# UbalToBal.net
KiCad netlist of a schematic drawn in EAGLE
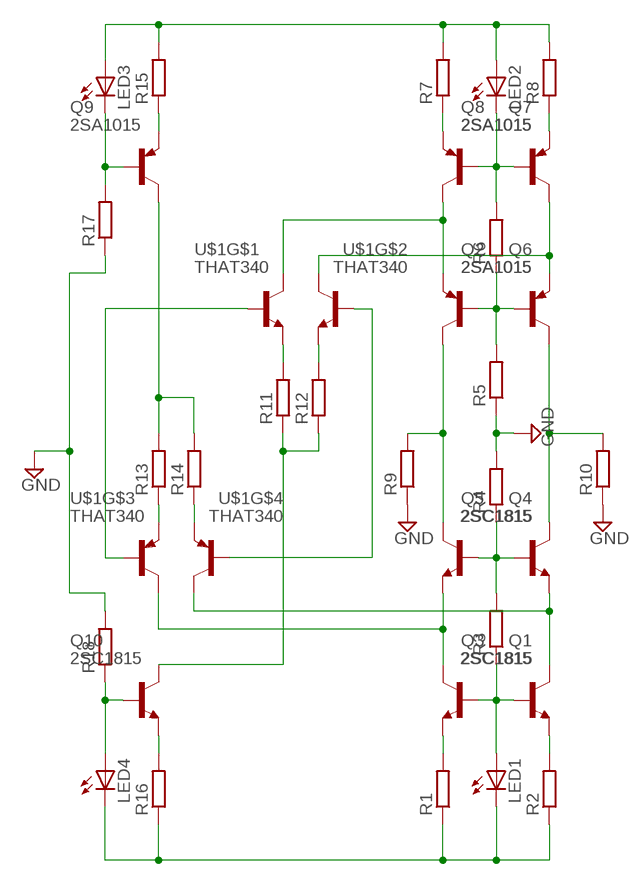
[diagram p0: schematic, sheet 1]

(export (version "E")
  (design (tool "Eeschema 10.0.6"))
  (components
    (comp (ref "LED1")
      (value "LED5MM")
      (footprint "eagle-import:LED5MM")
      (libsource (lib "eagle-import") (part "LED5MM"))
    )
    (comp (ref "LED2")
      (value "LED5MM")
      (footprint "eagle-import:LED5MM")
      (libsource (lib "eagle-import") (part "LED5MM"))
    )
    (comp (ref "LED3")
      (value "LED5MM")
      (footprint "eagle-import:LED5MM")
      (libsource (lib "eagle-import") (part "LED5MM"))
    )
    (comp (ref "LED4")
      (value "LED5MM")
      (footprint "eagle-import:LED5MM")
      (fields (field (name "SPICEPREFIX") "D"))
      (libsource (lib "eagle-import") (part "LED5MM"))
    )
    (comp (ref "Q1")
      (value "2SC1815")
      (footprint "eagle-import:TO92-BCE")
      (libsource (lib "eagle-import") (part "2SC1815"))
    )
    (comp (ref "Q2")
      (value "2SA1015")
      (footprint "eagle-import:TO92-BCE")
      (libsource (lib "eagle-import") (part "2SA1015"))
    )
    (comp (ref "Q3")
      (value "2SC1815")
      (footprint "eagle-import:TO92-BCE")
      (libsource (lib "eagle-import") (part "2SC1815"))
    )
    (comp (ref "Q4")
      (value "2SC1815")
      (footprint "eagle-import:TO92-BCE")
      (libsource (lib "eagle-import") (part "2SC1815"))
    )
    (comp (ref "Q5")
      (value "2SC1815")
      (footprint "eagle-import:TO92-BCE")
      (libsource (lib "eagle-import") (part "2SC1815"))
    )
    (comp (ref "Q6")
      (value "2SA1015")
      (footprint "eagle-import:TO92-BCE")
      (libsource (lib "eagle-import") (part "2SA1015"))
    )
    (comp (ref "Q7")
      (value "2SA1015")
      (footprint "eagle-import:TO92-BCE")
      (libsource (lib "eagle-import") (part "2SA1015"))
    )
    (comp (ref "Q8")
      (value "2SA1015")
      (footprint "eagle-import:TO92-BCE")
      (libsource (lib "eagle-import") (part "2SA1015"))
    )
    (comp (ref "Q9")
      (value "2SA1015")
      (footprint "eagle-import:TO92-BCE")
      (libsource (lib "eagle-import") (part "2SA1015"))
    )
    (comp (ref "Q10")
      (value "2SC1815")
      (footprint "eagle-import:TO92-BCE")
      (fields (field (name "SPICEPREFIX") "Q"))
      (libsource (lib "eagle-import") (part "2SC1815"))
    )
    (comp (ref "R1")
      (value "R-EU_MELF0204W")
      (footprint "eagle-import:MINI_MELF-0204W")
      (libsource (lib "eagle-import") (part "R-EU_MELF0204W"))
    )
    (comp (ref "R2")
      (value "R-EU_MELF0204W")
      (footprint "eagle-import:MINI_MELF-0204W")
      (libsource (lib "eagle-import") (part "R-EU_MELF0204W"))
    )
    (comp (ref "R3")
      (value "R-EU_MELF0204W")
      (footprint "eagle-import:MINI_MELF-0204W")
      (libsource (lib "eagle-import") (part "R-EU_MELF0204W"))
    )
    (comp (ref "R4")
      (value "R-EU_MELF0204W")
      (footprint "eagle-import:MINI_MELF-0204W")
      (libsource (lib "eagle-import") (part "R-EU_MELF0204W"))
    )
    (comp (ref "R5")
      (value "R-EU_MELF0204W")
      (footprint "eagle-import:MINI_MELF-0204W")
      (libsource (lib "eagle-import") (part "R-EU_MELF0204W"))
    )
    (comp (ref "R6")
      (value "R-EU_MELF0204W")
      (footprint "eagle-import:MINI_MELF-0204W")
      (libsource (lib "eagle-import") (part "R-EU_MELF0204W"))
    )
    (comp (ref "R7")
      (value "R-EU_MELF0204W")
      (footprint "eagle-import:MINI_MELF-0204W")
      (libsource (lib "eagle-import") (part "R-EU_MELF0204W"))
    )
    (comp (ref "R8")
      (value "R-EU_MELF0204W")
      (footprint "eagle-import:MINI_MELF-0204W")
      (libsource (lib "eagle-import") (part "R-EU_MELF0204W"))
    )
    (comp (ref "R9")
      (value "R-EU_MELF0204W")
      (footprint "eagle-import:MINI_MELF-0204W")
      (libsource (lib "eagle-import") (part "R-EU_MELF0204W"))
    )
    (comp (ref "R10")
      (value "R-EU_MELF0204W")
      (footprint "eagle-import:MINI_MELF-0204W")
      (libsource (lib "eagle-import") (part "R-EU_MELF0204W"))
    )
    (comp (ref "R11")
      (value "R-EU_MELF0204W")
      (footprint "eagle-import:MINI_MELF-0204W")
      (libsource (lib "eagle-import") (part "R-EU_MELF0204W"))
    )
    (comp (ref "R12")
      (value "R-EU_MELF0204W")
      (footprint "eagle-import:MINI_MELF-0204W")
      (libsource (lib "eagle-import") (part "R-EU_MELF0204W"))
    )
    (comp (ref "R13")
      (value "R-EU_MELF0204W")
      (footprint "eagle-import:MINI_MELF-0204W")
      (libsource (lib "eagle-import") (part "R-EU_MELF0204W"))
    )
    (comp (ref "R14")
      (value "R-EU_MELF0204W")
      (footprint "eagle-import:MINI_MELF-0204W")
      (libsource (lib "eagle-import") (part "R-EU_MELF0204W"))
    )
    (comp (ref "R15")
      (value "R-EU_MELF0204W")
      (footprint "eagle-import:MINI_MELF-0204W")
      (libsource (lib "eagle-import") (part "R-EU_MELF0204W"))
    )
    (comp (ref "R16")
      (value "R-EU_MELF0204W")
      (footprint "eagle-import:MINI_MELF-0204W")
      (fields (field (name "SPICEPREFIX") "R"))
      (libsource (lib "eagle-import") (part "R-EU_MELF0204W"))
    )
    (comp (ref "R17")
      (value "R-EU_MELF0204W")
      (footprint "eagle-import:MINI_MELF-0204W")
      (libsource (lib "eagle-import") (part "R-EU_MELF0204W"))
    )
    (comp (ref "R18")
      (value "R-EU_MELF0204W")
      (footprint "eagle-import:MINI_MELF-0204W")
      (libsource (lib "eagle-import") (part "R-EU_MELF0204W"))
    )
    (comp (ref "U$1")
      (value "THAT340")
      (footprint "eagle-import:DIP254P762X510-14")
      (libsource (lib "eagle-import") (part "THAT340"))
    )
  )
  (nets
    (net (code "1") (name "GND") (class "Default")
      (node (ref "R10") (pin "1") (pinfunction "1_1") (pintype "passive"))
      (node (ref "R17") (pin "1") (pinfunction "1_1") (pintype "passive"))
      (node (ref "R18") (pin "2") (pinfunction "2_2") (pintype "passive"))
      (node (ref "R4") (pin "2") (pinfunction "2_2") (pintype "passive"))
      (node (ref "R5") (pin "1") (pinfunction "1_1") (pintype "passive"))
      (node (ref "R9") (pin "1") (pinfunction "1_1") (pintype "passive"))
    )
    (net (code "2") (name "Net-(LED1-C)") (class "Default")
      (node (ref "LED1") (pin "K") (pinfunction "C_K") (pintype "passive"))
      (node (ref "LED4") (pin "K") (pinfunction "C_K") (pintype "passive"))
      (node (ref "R1") (pin "1") (pinfunction "1_1") (pintype "passive"))
      (node (ref "R16") (pin "1") (pinfunction "1_1") (pintype "passive"))
      (node (ref "R2") (pin "1") (pinfunction "1_1") (pintype "passive"))
    )
    (net (code "3") (name "Net-(LED1-PadA)") (class "Default")
      (node (ref "LED1") (pin "A") (pinfunction "A_A") (pintype "passive"))
      (node (ref "Q1") (pin "B") (pinfunction "B_B") (pintype "passive"))
      (node (ref "Q3") (pin "B") (pinfunction "B_B") (pintype "passive"))
      (node (ref "R3") (pin "1") (pinfunction "1_1") (pintype "passive"))
    )
    (net (code "4") (name "Net-(LED2-C)") (class "Default")
      (node (ref "LED2") (pin "K") (pinfunction "C_K") (pintype "passive"))
      (node (ref "Q7") (pin "B") (pinfunction "B_B") (pintype "passive"))
      (node (ref "Q8") (pin "B") (pinfunction "B_B") (pintype "passive"))
      (node (ref "R6") (pin "2") (pinfunction "2_2") (pintype "passive"))
    )
    (net (code "5") (name "Net-(LED2-PadA)") (class "Default")
      (node (ref "LED2") (pin "A") (pinfunction "A_A") (pintype "passive"))
      (node (ref "LED3") (pin "A") (pinfunction "A_A") (pintype "passive"))
      (node (ref "R15") (pin "2") (pinfunction "2_2") (pintype "passive"))
      (node (ref "R7") (pin "2") (pinfunction "2_2") (pintype "passive"))
      (node (ref "R8") (pin "2") (pinfunction "2_2") (pintype "passive"))
    )
    (net (code "6") (name "Net-(LED3-C)") (class "Default")
      (node (ref "LED3") (pin "K") (pinfunction "C_K") (pintype "passive"))
      (node (ref "Q9") (pin "B") (pinfunction "B_B") (pintype "passive"))
      (node (ref "R17") (pin "2") (pinfunction "2_2") (pintype "passive"))
    )
    (net (code "7") (name "Net-(LED4-PadA)") (class "Default")
      (node (ref "LED4") (pin "A") (pinfunction "A_A") (pintype "passive"))
      (node (ref "Q10") (pin "B") (pinfunction "B_B") (pintype "passive"))
      (node (ref "R18") (pin "1") (pinfunction "1_1") (pintype "passive"))
    )
    (net (code "8") (name "Net-(Q1-PadE)") (class "Default")
      (node (ref "Q1") (pin "E") (pinfunction "E_E") (pintype "passive"))
      (node (ref "R1") (pin "2") (pinfunction "2_2") (pintype "passive"))
    )
    (net (code "9") (name "Net-(Q2-PadB)") (class "Default")
      (node (ref "Q2") (pin "B") (pinfunction "B_B") (pintype "passive"))
      (node (ref "Q6") (pin "B") (pinfunction "B_B") (pintype "passive"))
      (node (ref "R5") (pin "2") (pinfunction "2_2") (pintype "passive"))
      (node (ref "R6") (pin "1") (pinfunction "1_1") (pintype "passive"))
    )
    (net (code "10") (name "Net-(Q2-PadC)") (class "Default")
      (node (ref "Q2") (pin "C") (pinfunction "C_C") (pintype "passive"))
      (node (ref "Q5") (pin "C") (pinfunction "C_C") (pintype "passive"))
      (node (ref "R10") (pin "2") (pinfunction "2_2") (pintype "passive"))
    )
    (net (code "11") (name "Net-(Q3-PadE)") (class "Default")
      (node (ref "Q3") (pin "E") (pinfunction "E_E") (pintype "passive"))
      (node (ref "R2") (pin "2") (pinfunction "2_2") (pintype "passive"))
    )
    (net (code "12") (name "Net-(Q4-PadB)") (class "Default")
      (node (ref "Q4") (pin "B") (pinfunction "B_B") (pintype "passive"))
      (node (ref "Q5") (pin "B") (pinfunction "B_B") (pintype "passive"))
      (node (ref "R3") (pin "2") (pinfunction "2_2") (pintype "passive"))
      (node (ref "R4") (pin "1") (pinfunction "1_1") (pintype "passive"))
    )
    (net (code "13") (name "Net-(Q4-PadC)") (class "Default")
      (node (ref "Q4") (pin "C") (pinfunction "C_C") (pintype "passive"))
      (node (ref "Q6") (pin "C") (pinfunction "C_C") (pintype "passive"))
      (node (ref "R9") (pin "2") (pinfunction "2_2") (pintype "passive"))
    )
    (net (code "14") (name "Net-(Q7-PadE)") (class "Default")
      (node (ref "Q7") (pin "E") (pinfunction "E_E") (pintype "passive"))
      (node (ref "R7") (pin "1") (pinfunction "1_1") (pintype "passive"))
    )
    (net (code "15") (name "Net-(Q8-PadE)") (class "Default")
      (node (ref "Q8") (pin "E") (pinfunction "E_E") (pintype "passive"))
      (node (ref "R8") (pin "1") (pinfunction "1_1") (pintype "passive"))
    )
    (net (code "16") (name "Net-(Q9-PadC)") (class "Default")
      (node (ref "Q9") (pin "C") (pinfunction "C_C") (pintype "passive"))
      (node (ref "R13") (pin "2") (pinfunction "2_2") (pintype "passive"))
      (node (ref "R14") (pin "2") (pinfunction "2_2") (pintype "passive"))
    )
    (net (code "17") (name "Net-(Q9-PadE)") (class "Default")
      (node (ref "Q9") (pin "E") (pinfunction "E_E") (pintype "passive"))
      (node (ref "R15") (pin "1") (pinfunction "1_1") (pintype "passive"))
    )
    (net (code "18") (name "Net-(Q10-PadC)") (class "Default")
      (node (ref "Q10") (pin "C") (pinfunction "C_C") (pintype "passive"))
      (node (ref "R11") (pin "1") (pinfunction "1_1") (pintype "passive"))
      (node (ref "R12") (pin "1") (pinfunction "1_1") (pintype "passive"))
    )
    (net (code "19") (name "Net-(Q10-PadE)") (class "Default")
      (node (ref "Q10") (pin "E") (pinfunction "E_E") (pintype "passive"))
      (node (ref "R16") (pin "2") (pinfunction "2_2") (pintype "passive"))
    )
    (net (code "20") (name "Net-(U$1A-B)") (class "Default")
      (node (ref "U$1") (pin "2") (pinfunction "B_2") (pintype "passive"))
      (node (ref "U$1") (pin "6") (pinfunction "B_6") (pintype "passive"))
    )
    (net (code "21") (name "Net-(U$1A-C)") (class "Default")
      (node (ref "Q6") (pin "E") (pinfunction "E_E") (pintype "passive"))
      (node (ref "Q7") (pin "C") (pinfunction "C_C") (pintype "passive"))
      (node (ref "U$1") (pin "1") (pinfunction "C_1") (pintype "passive"))
    )
    (net (code "22") (name "Net-(U$1A-E)") (class "Default")
      (node (ref "R11") (pin "2") (pinfunction "2_2") (pintype "passive"))
      (node (ref "U$1") (pin "3") (pinfunction "E_3") (pintype "passive"))
    )
    (net (code "23") (name "Net-(U$1B-B)") (class "Default")
      (node (ref "U$1") (pin "13") (pinfunction "B_13") (pintype "passive"))
      (node (ref "U$1") (pin "9") (pinfunction "B_9") (pintype "passive"))
    )
    (net (code "24") (name "Net-(U$1B-C)") (class "Default")
      (node (ref "Q2") (pin "E") (pinfunction "E_E") (pintype "passive"))
      (node (ref "Q8") (pin "C") (pinfunction "C_C") (pintype "passive"))
      (node (ref "U$1") (pin "14") (pinfunction "C_14") (pintype "passive"))
    )
    (net (code "25") (name "Net-(U$1B-E)") (class "Default")
      (node (ref "R12") (pin "2") (pinfunction "2_2") (pintype "passive"))
      (node (ref "U$1") (pin "12") (pinfunction "E_12") (pintype "passive"))
    )
    (net (code "26") (name "Net-(U$1C-C)") (class "Default")
      (node (ref "Q1") (pin "C") (pinfunction "C_C") (pintype "passive"))
      (node (ref "Q4") (pin "E") (pinfunction "E_E") (pintype "passive"))
      (node (ref "U$1") (pin "7") (pinfunction "C_7") (pintype "passive"))
    )
    (net (code "27") (name "Net-(U$1C-E)") (class "Default")
      (node (ref "R13") (pin "1") (pinfunction "1_1") (pintype "passive"))
      (node (ref "U$1") (pin "5") (pinfunction "E_5") (pintype "passive"))
    )
    (net (code "28") (name "Net-(U$1D-C)") (class "Default")
      (node (ref "Q3") (pin "C") (pinfunction "C_C") (pintype "passive"))
      (node (ref "Q5") (pin "E") (pinfunction "E_E") (pintype "passive"))
      (node (ref "U$1") (pin "8") (pinfunction "C_8") (pintype "passive"))
    )
    (net (code "29") (name "Net-(U$1D-E)") (class "Default")
      (node (ref "R14") (pin "1") (pinfunction "1_1") (pintype "passive"))
      (node (ref "U$1") (pin "10") (pinfunction "E_10") (pintype "passive"))
    )
  )
)
